# FOC_ESC_V1_1.net
KiCad netlist of a schematic drawn in Altium Designer
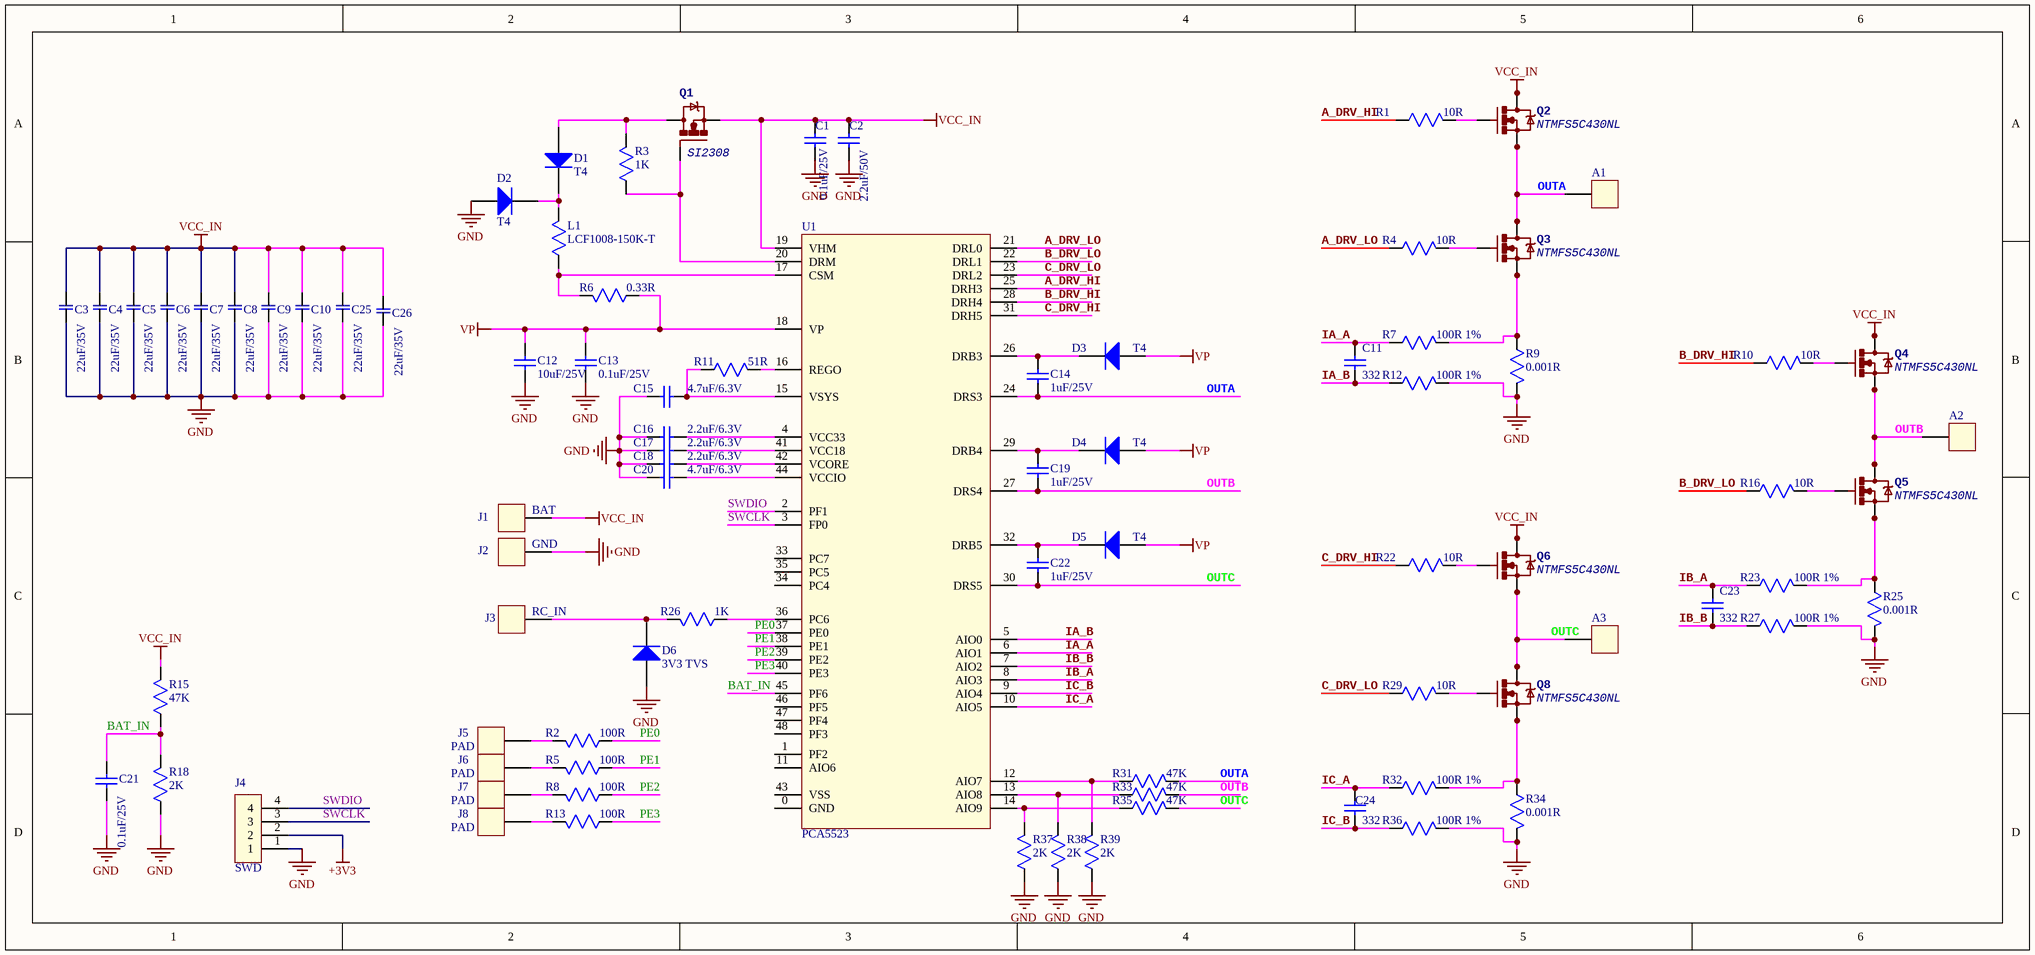
[diagram p0: FOC_ESC V1.1.SchDoc]

(export (version "E")
  (design (tool "Eeschema 10.0.6"))
  (components
    (comp (ref "A1") (value "~") (footprint "PAD-1  4*3") (libsource (lib "") (part "PAD_1")))
    (comp (ref "A2") (value "~") (footprint "PAD-1  4*3") (libsource (lib "") (part "PAD_1")))
    (comp (ref "A3") (value "~") (footprint "PAD-1  4*3") (libsource (lib "") (part "PAD_1")))
    (comp (ref "C1")
      (value "0.1uF/25V")
      (footprint "0603-RES")
      (fields (field (name "PUBLISHER") "Altium Limited"))
      (libsource (lib "DYS-XM30A V3.0") (part "Cap"))
    )
    (comp (ref "C2")
      (value "2.2uF/50V")
      (footprint "0805-RES")
      (fields (field (name "PUBLISHER") "Altium Limited"))
      (libsource (lib "DYS-XM30A V3.0") (part "Cap"))
    )
    (comp (ref "C3") (value "22uF/35V") (footprint "1206-RES") (libsource (lib "USER-2016") (part "C")))
    (comp (ref "C4") (value "22uF/35V") (footprint "1206-RES") (libsource (lib "USER-2016") (part "C")))
    (comp (ref "C5") (value "22uF/35V") (footprint "1206-RES") (libsource (lib "USER-2016") (part "C")))
    (comp (ref "C6") (value "22uF/35V") (footprint "1206-RES") (libsource (lib "USER-2016") (part "C")))
    (comp (ref "C7") (value "22uF/35V") (footprint "1206-RES") (libsource (lib "USER-2016") (part "C")))
    (comp (ref "C8") (value "22uF/35V") (footprint "1206-RES") (libsource (lib "USER-2016") (part "C")))
    (comp (ref "C9") (value "22uF/35V") (footprint "1206-RES") (libsource (lib "USER-2016") (part "C")))
    (comp (ref "C10") (value "22uF/35V") (footprint "1206-RES") (libsource (lib "USER-2016") (part "C")))
    (comp (ref "C11")
      (value "332")
      (footprint "0402-RES")
      (fields (field (name "PUBLISHER") "Altium Limited"))
      (libsource (lib "DYS-XM30A V3.0") (part "Cap"))
    )
    (comp (ref "C12")
      (value "10uF/25V")
      (footprint "0805-RES")
      (fields (field (name "PUBLISHER") "Altium Limited"))
      (libsource (lib "DYS-XM30A V3.0") (part "Cap"))
    )
    (comp (ref "C13")
      (value "0.1uF/25V")
      (footprint "0603-RES")
      (fields (field (name "PUBLISHER") "Altium Limited"))
      (libsource (lib "DYS-XM30A V3.0") (part "Cap"))
    )
    (comp (ref "C14")
      (value "1uF/25V")
      (footprint "0805-RES")
      (fields (field (name "PUBLISHER") "Altium Limited"))
      (libsource (lib "DYS-XM30A V3.0") (part "Cap"))
    )
    (comp (ref "C15")
      (value "4.7uF/6.3V")
      (footprint "0402-RES")
      (fields (field (name "PUBLISHER") "Altium Limited"))
      (libsource (lib "DYS-XM30A V3.0") (part "Cap"))
    )
    (comp (ref "C16")
      (value "2.2uF/6.3V")
      (footprint "0402-RES")
      (fields (field (name "PUBLISHER") "Altium Limited"))
      (libsource (lib "DYS-XM30A V3.0") (part "Cap"))
    )
    (comp (ref "C17")
      (value "2.2uF/6.3V")
      (footprint "0402-RES")
      (fields (field (name "PUBLISHER") "Altium Limited"))
      (libsource (lib "DYS-XM30A V3.0") (part "Cap"))
    )
    (comp (ref "C18")
      (value "2.2uF/6.3V")
      (footprint "0402-RES")
      (fields (field (name "PUBLISHER") "Altium Limited"))
      (libsource (lib "DYS-XM30A V3.0") (part "Cap"))
    )
    (comp (ref "C19")
      (value "1uF/25V")
      (footprint "0805-RES")
      (fields (field (name "PUBLISHER") "Altium Limited"))
      (libsource (lib "DYS-XM30A V3.0") (part "Cap"))
    )
    (comp (ref "C20")
      (value "4.7uF/6.3V")
      (footprint "0402-RES")
      (fields (field (name "PUBLISHER") "Altium Limited"))
      (libsource (lib "DYS-XM30A V3.0") (part "Cap"))
    )
    (comp (ref "C21")
      (value "0.1uF/25V")
      (footprint "0402-RES")
      (fields (field (name "PUBLISHER") "Altium Limited"))
      (libsource (lib "DYS-XM30A V3.0") (part "Cap"))
    )
    (comp (ref "C22")
      (value "1uF/25V")
      (footprint "0805-RES")
      (fields (field (name "PUBLISHER") "Altium Limited"))
      (libsource (lib "DYS-XM30A V3.0") (part "Cap"))
    )
    (comp (ref "C23")
      (value "332")
      (footprint "0402-RES")
      (fields (field (name "PUBLISHER") "Altium Limited"))
      (libsource (lib "DYS-XM30A V3.0") (part "Cap"))
    )
    (comp (ref "C24")
      (value "332")
      (footprint "0402-RES")
      (fields (field (name "PUBLISHER") "Altium Limited"))
      (libsource (lib "DYS-XM30A V3.0") (part "Cap"))
    )
    (comp (ref "C25") (value "22uF/35V") (footprint "1206-RES") (libsource (lib "USER-2016") (part "C")))
    (comp (ref "C26") (value "22uF/35V") (footprint "1206-RES") (libsource (lib "USER-2016") (part "C")))
    (comp (ref "D1")
      (value "T4")
      (footprint "SOD323")
      (fields (field (name "PUBLISHER") "Altium Limited"))
      (libsource (lib "DYS-XM30A V3.0") (part "Diode"))
    )
    (comp (ref "D2")
      (value "T4")
      (footprint "SOD323")
      (fields (field (name "PUBLISHER") "Altium Limited"))
      (libsource (lib "DYS-XM30A V3.0") (part "Diode"))
    )
    (comp (ref "D3")
      (value "T4")
      (footprint "SOD323")
      (fields (field (name "PUBLISHER") "Altium Limited"))
      (libsource (lib "DYS-XM30A V3.0") (part "Diode"))
    )
    (comp (ref "D4")
      (value "T4")
      (footprint "SOD323")
      (fields (field (name "PUBLISHER") "Altium Limited"))
      (libsource (lib "DYS-XM30A V3.0") (part "Diode"))
    )
    (comp (ref "D5")
      (value "T4")
      (footprint "SOD323")
      (fields (field (name "PUBLISHER") "Altium Limited"))
      (libsource (lib "DYS-XM30A V3.0") (part "Diode"))
    )
    (comp (ref "D6")
      (value "3V3 TVS")
      (footprint "SOD323")
      (fields (field (name "PUBLISHER") "Altium Limited"))
      (libsource (lib "DYS-XM30A V3.0") (part "Diode"))
    )
    (comp (ref "J1") (value "BAT") (footprint "PAD-1  4*3") (libsource (lib "USER-2016") (part "PAD")))
    (comp (ref "J2") (value "GND") (footprint "PAD-1  4*3") (libsource (lib "USER-2016") (part "PAD")))
    (comp (ref "J3") (value "RC_IN") (footprint "PAD-1  2*1.5") (libsource (lib "USER-2016") (part "PAD")))
    (comp (ref "J4") (value "SWD") (footprint "1.0-4p") (libsource (lib "USER-2016") (part "J_4P")))
    (comp (ref "J5") (value "PAD") (footprint "PAD-1  0.8*1.2") (libsource (lib "USER-2016") (part "PAD")))
    (comp (ref "J6") (value "PAD") (footprint "PAD-1  0.8*1.2") (libsource (lib "USER-2016") (part "PAD")))
    (comp (ref "J7") (value "PAD") (footprint "PAD-1  0.8*1.2") (libsource (lib "USER-2016") (part "PAD")))
    (comp (ref "J8") (value "PAD") (footprint "PAD-1  0.8*1.2") (libsource (lib "USER-2016") (part "PAD")))
    (comp (ref "L1")
      (value "LCF1008-150K-T")
      (footprint "LCF1008-RES")
      (libsource (lib "USER-2016") (part "R"))
    )
    (comp (ref "Q1") (value "SI2308") (footprint "SOT-23") (libsource (lib "USER-2016") (part "P-MOS")))
    (comp (ref "Q2")
      (value "NTMFS5C430NL")
      (footprint "DFN5*6")
      (libsource (lib "USER-2016") (part "AON7418"))
    )
    (comp (ref "Q3")
      (value "NTMFS5C430NL")
      (footprint "DFN5*6")
      (libsource (lib "USER-2016") (part "AON7418"))
    )
    (comp (ref "Q4")
      (value "NTMFS5C430NL")
      (footprint "DFN5*6")
      (libsource (lib "USER-2016") (part "AON7418"))
    )
    (comp (ref "Q5")
      (value "NTMFS5C430NL")
      (footprint "DFN5*6")
      (libsource (lib "USER-2016") (part "AON7418"))
    )
    (comp (ref "Q6")
      (value "NTMFS5C430NL")
      (footprint "DFN5*6")
      (libsource (lib "USER-2016") (part "AON7418"))
    )
    (comp (ref "Q8")
      (value "NTMFS5C430NL")
      (footprint "DFN5*6")
      (libsource (lib "USER-2016") (part "AON7418"))
    )
    (comp (ref "R1") (value "10R") (footprint "0402-RES") (libsource (lib "USER-2016") (part "R")))
    (comp (ref "R2") (value "100R") (footprint "0402-RES") (libsource (lib "USER-2016") (part "R")))
    (comp (ref "R3") (value "1K") (footprint "0402-RES") (libsource (lib "USER-2016") (part "R")))
    (comp (ref "R4") (value "10R") (footprint "0402-RES") (libsource (lib "USER-2016") (part "R")))
    (comp (ref "R5") (value "100R") (footprint "0402-RES") (libsource (lib "USER-2016") (part "R")))
    (comp (ref "R6") (value "0.33R") (footprint "0805-RES") (libsource (lib "USER-2016") (part "R")))
    (comp (ref "R7") (value "100R 1%") (footprint "0402-RES") (libsource (lib "USER-2016") (part "R")))
    (comp (ref "R8") (value "100R") (footprint "0402-RES") (libsource (lib "USER-2016") (part "R")))
    (comp (ref "R9") (value "0.001R") (footprint "2512-RES") (libsource (lib "USER-2016") (part "R")))
    (comp (ref "R10") (value "10R") (footprint "0402-RES") (libsource (lib "USER-2016") (part "R")))
    (comp (ref "R11") (value "51R") (footprint "0402-RES") (libsource (lib "USER-2016") (part "R")))
    (comp (ref "R12") (value "100R 1%") (footprint "0402-RES") (libsource (lib "USER-2016") (part "R")))
    (comp (ref "R13") (value "100R") (footprint "0402-RES") (libsource (lib "USER-2016") (part "R")))
    (comp (ref "R15") (value "47K") (footprint "0402-RES") (libsource (lib "USER-2016") (part "R")))
    (comp (ref "R16") (value "10R") (footprint "0402-RES") (libsource (lib "USER-2016") (part "R")))
    (comp (ref "R18") (value "2K") (footprint "0402-RES") (libsource (lib "USER-2016") (part "R")))
    (comp (ref "R22") (value "10R") (footprint "0402-RES") (libsource (lib "USER-2016") (part "R")))
    (comp (ref "R23") (value "100R 1%") (footprint "0402-RES") (libsource (lib "USER-2016") (part "R")))
    (comp (ref "R25") (value "0.001R") (footprint "2512-RES") (libsource (lib "USER-2016") (part "R")))
    (comp (ref "R26") (value "1K") (footprint "0402-RES") (libsource (lib "USER-2016") (part "R")))
    (comp (ref "R27") (value "100R 1%") (footprint "0402-RES") (libsource (lib "USER-2016") (part "R")))
    (comp (ref "R29") (value "10R") (footprint "0402-RES") (libsource (lib "USER-2016") (part "R")))
    (comp (ref "R31") (value "47K") (footprint "0402-RES") (libsource (lib "USER-2016") (part "R")))
    (comp (ref "R32") (value "100R 1%") (footprint "0402-RES") (libsource (lib "USER-2016") (part "R")))
    (comp (ref "R33") (value "47K") (footprint "0402-RES") (libsource (lib "USER-2016") (part "R")))
    (comp (ref "R34") (value "0.001R") (footprint "2512-RES") (libsource (lib "USER-2016") (part "R")))
    (comp (ref "R35") (value "47K") (footprint "0402-RES") (libsource (lib "USER-2016") (part "R")))
    (comp (ref "R36") (value "100R 1%") (footprint "0402-RES") (libsource (lib "USER-2016") (part "R")))
    (comp (ref "R37") (value "2K") (footprint "0402-RES") (libsource (lib "USER-2016") (part "R")))
    (comp (ref "R38") (value "2K") (footprint "0402-RES") (libsource (lib "USER-2016") (part "R")))
    (comp (ref "R39") (value "2K") (footprint "0402-RES") (libsource (lib "USER-2016") (part "R")))
    (comp (ref "U1") (value "PCA5523") (footprint "QFN48") (libsource (lib "USER-2016") (part "PCA5523")))
  )
  (nets
    (net (code "1") (name "+3V3") (class "Default")
      (node (ref "J4") (pin "2") (pinfunction "2_2") (pintype "passive"))
    )
    (net (code "2") (name "/A_DRV_HI") (class "Default")
      (node (ref "R1") (pin "1") (pinfunction "1_1") (pintype "passive"))
      (node (ref "U1") (pin "25") (pinfunction "DRH3_25") (pintype "passive"))
    )
    (net (code "3") (name "/A_DRV_LO") (class "Default")
      (node (ref "R4") (pin "1") (pinfunction "1_1") (pintype "passive"))
      (node (ref "U1") (pin "21") (pinfunction "DRL0_21") (pintype "passive"))
    )
    (net (code "4") (name "/BAT_IN") (class "Default")
      (node (ref "C21") (pin "1") (pinfunction "1_1") (pintype "passive"))
      (node (ref "R15") (pin "1") (pinfunction "1_1") (pintype "passive"))
      (node (ref "R18") (pin "2") (pinfunction "2_2") (pintype "passive"))
      (node (ref "U1") (pin "45") (pinfunction "PF6_45") (pintype "passive"))
    )
    (net (code "5") (name "/B_DRV_HI") (class "Default")
      (node (ref "R10") (pin "1") (pinfunction "1_1") (pintype "passive"))
      (node (ref "U1") (pin "28") (pinfunction "DRH4_28") (pintype "passive"))
    )
    (net (code "6") (name "/B_DRV_LO") (class "Default")
      (node (ref "R16") (pin "1") (pinfunction "1_1") (pintype "passive"))
      (node (ref "U1") (pin "22") (pinfunction "DRL1_22") (pintype "passive"))
    )
    (net (code "7") (name "/C_DRV_HI") (class "Default")
      (node (ref "R22") (pin "1") (pinfunction "1_1") (pintype "passive"))
      (node (ref "U1") (pin "31") (pinfunction "DRH5_31") (pintype "passive"))
    )
    (net (code "8") (name "/C_DRV_LO") (class "Default")
      (node (ref "R29") (pin "1") (pinfunction "1_1") (pintype "passive"))
      (node (ref "U1") (pin "23") (pinfunction "DRL2_23") (pintype "passive"))
    )
    (net (code "9") (name "/IA_A") (class "Default")
      (node (ref "C11") (pin "1") (pinfunction "1_1") (pintype "passive"))
      (node (ref "R7") (pin "1") (pinfunction "1_1") (pintype "passive"))
      (node (ref "U1") (pin "6") (pinfunction "AIO1_6") (pintype "passive"))
    )
    (net (code "10") (name "/IA_B") (class "Default")
      (node (ref "C11") (pin "2") (pinfunction "2_2") (pintype "passive"))
      (node (ref "R12") (pin "1") (pinfunction "1_1") (pintype "passive"))
      (node (ref "U1") (pin "5") (pinfunction "AIO0_5") (pintype "passive"))
    )
    (net (code "11") (name "/IB_A") (class "Default")
      (node (ref "C23") (pin "1") (pinfunction "1_1") (pintype "passive"))
      (node (ref "R23") (pin "1") (pinfunction "1_1") (pintype "passive"))
      (node (ref "U1") (pin "8") (pinfunction "AIO3_8") (pintype "passive"))
    )
    (net (code "12") (name "/IB_B") (class "Default")
      (node (ref "C23") (pin "2") (pinfunction "2_2") (pintype "passive"))
      (node (ref "R27") (pin "1") (pinfunction "1_1") (pintype "passive"))
      (node (ref "U1") (pin "7") (pinfunction "AIO2_7") (pintype "passive"))
    )
    (net (code "13") (name "/IC_A") (class "Default")
      (node (ref "C24") (pin "1") (pinfunction "1_1") (pintype "passive"))
      (node (ref "R32") (pin "1") (pinfunction "1_1") (pintype "passive"))
      (node (ref "U1") (pin "10") (pinfunction "AIO5_10") (pintype "passive"))
    )
    (net (code "14") (name "/IC_B") (class "Default")
      (node (ref "C24") (pin "2") (pinfunction "2_2") (pintype "passive"))
      (node (ref "R36") (pin "1") (pinfunction "1_1") (pintype "passive"))
      (node (ref "U1") (pin "9") (pinfunction "AIO4_9") (pintype "passive"))
    )
    (net (code "15") (name "/OUTA") (class "Default")
      (node (ref "A1") (pin "1") (pinfunction "1_1") (pintype "passive"))
      (node (ref "C14") (pin "2") (pinfunction "2_2") (pintype "passive"))
      (node (ref "Q2") (pin "3") (pinfunction "S_3") (pintype "passive"))
      (node (ref "Q3") (pin "5") (pinfunction "D_5") (pintype "passive"))
      (node (ref "R31") (pin "2") (pinfunction "2_2") (pintype "passive"))
      (node (ref "U1") (pin "24") (pinfunction "DRS3_24") (pintype "passive"))
    )
    (net (code "16") (name "/OUTB") (class "Default")
      (node (ref "A2") (pin "1") (pinfunction "1_1") (pintype "passive"))
      (node (ref "C19") (pin "2") (pinfunction "2_2") (pintype "passive"))
      (node (ref "Q4") (pin "3") (pinfunction "S_3") (pintype "passive"))
      (node (ref "Q5") (pin "5") (pinfunction "D_5") (pintype "passive"))
      (node (ref "R33") (pin "2") (pinfunction "2_2") (pintype "passive"))
      (node (ref "U1") (pin "27") (pinfunction "DRS4_27") (pintype "passive"))
    )
    (net (code "17") (name "/OUTC") (class "Default")
      (node (ref "A3") (pin "1") (pinfunction "1_1") (pintype "passive"))
      (node (ref "C22") (pin "2") (pinfunction "2_2") (pintype "passive"))
      (node (ref "Q6") (pin "3") (pinfunction "S_3") (pintype "passive"))
      (node (ref "Q8") (pin "5") (pinfunction "D_5") (pintype "passive"))
      (node (ref "R35") (pin "2") (pinfunction "2_2") (pintype "passive"))
      (node (ref "U1") (pin "30") (pinfunction "DRS5_30") (pintype "passive"))
    )
    (net (code "18") (name "/PE0") (class "Default")
      (node (ref "R2") (pin "1") (pinfunction "1_1") (pintype "passive"))
      (node (ref "U1") (pin "37") (pinfunction "PE0_37") (pintype "passive"))
    )
    (net (code "19") (name "/PE1") (class "Default")
      (node (ref "R5") (pin "1") (pinfunction "1_1") (pintype "passive"))
      (node (ref "U1") (pin "38") (pinfunction "PE1_38") (pintype "passive"))
    )
    (net (code "20") (name "/PE2") (class "Default")
      (node (ref "R8") (pin "1") (pinfunction "1_1") (pintype "passive"))
      (node (ref "U1") (pin "39") (pinfunction "PE2_39") (pintype "passive"))
    )
    (net (code "21") (name "/PE3") (class "Default")
      (node (ref "R13") (pin "1") (pinfunction "1_1") (pintype "passive"))
      (node (ref "U1") (pin "40") (pinfunction "PE3_40") (pintype "passive"))
    )
    (net (code "22") (name "/SWCLK") (class "Default")
      (node (ref "J4") (pin "3") (pinfunction "3_3") (pintype "passive"))
      (node (ref "U1") (pin "3") (pinfunction "FP0_3") (pintype "passive"))
    )
    (net (code "23") (name "/SWDIO") (class "Default")
      (node (ref "J4") (pin "4") (pinfunction "4_4") (pintype "passive"))
      (node (ref "U1") (pin "2") (pinfunction "PF1_2") (pintype "passive"))
    )
    (net (code "24") (name "GND") (class "Default")
      (node (ref "C1") (pin "2") (pinfunction "2_2") (pintype "passive"))
      (node (ref "C10") (pin "2") (pinfunction "2_2") (pintype "passive"))
      (node (ref "C12") (pin "2") (pinfunction "2_2") (pintype "passive"))
      (node (ref "C13") (pin "2") (pinfunction "2_2") (pintype "passive"))
      (node (ref "C15") (pin "1") (pinfunction "1_1") (pintype "passive"))
      (node (ref "C16") (pin "1") (pinfunction "1_1") (pintype "passive"))
      (node (ref "C17") (pin "1") (pinfunction "1_1") (pintype "passive"))
      (node (ref "C18") (pin "1") (pinfunction "1_1") (pintype "passive"))
      (node (ref "C2") (pin "2") (pinfunction "2_2") (pintype "passive"))
      (node (ref "C20") (pin "1") (pinfunction "1_1") (pintype "passive"))
      (node (ref "C21") (pin "2") (pinfunction "2_2") (pintype "passive"))
      (node (ref "C25") (pin "2") (pinfunction "2_2") (pintype "passive"))
      (node (ref "C26") (pin "2") (pinfunction "2_2") (pintype "passive"))
      (node (ref "C3") (pin "2") (pinfunction "2_2") (pintype "passive"))
      (node (ref "C4") (pin "2") (pinfunction "2_2") (pintype "passive"))
      (node (ref "C5") (pin "2") (pinfunction "2_2") (pintype "passive"))
      (node (ref "C6") (pin "2") (pinfunction "2_2") (pintype "passive"))
      (node (ref "C7") (pin "2") (pinfunction "2_2") (pintype "passive"))
      (node (ref "C8") (pin "2") (pinfunction "2_2") (pintype "passive"))
      (node (ref "C9") (pin "2") (pinfunction "2_2") (pintype "passive"))
      (node (ref "D2") (pin "1") (pinfunction "A_1") (pintype "passive"))
      (node (ref "D6") (pin "1") (pinfunction "A_1") (pintype "passive"))
      (node (ref "J2") (pin "1") (pinfunction "1_1") (pintype "passive"))
      (node (ref "J4") (pin "1") (pinfunction "1_1") (pintype "passive"))
      (node (ref "R12") (pin "2") (pinfunction "2_2") (pintype "passive"))
      (node (ref "R18") (pin "1") (pinfunction "1_1") (pintype "passive"))
      (node (ref "R25") (pin "2") (pinfunction "2_2") (pintype "passive"))
      (node (ref "R27") (pin "2") (pinfunction "2_2") (pintype "passive"))
      (node (ref "R34") (pin "2") (pinfunction "2_2") (pintype "passive"))
      (node (ref "R36") (pin "2") (pinfunction "2_2") (pintype "passive"))
      (node (ref "R37") (pin "1") (pinfunction "1_1") (pintype "passive"))
      (node (ref "R38") (pin "1") (pinfunction "1_1") (pintype "passive"))
      (node (ref "R39") (pin "1") (pinfunction "1_1") (pintype "passive"))
      (node (ref "R9") (pin "2") (pinfunction "2_2") (pintype "passive"))
    )
    (net (code "25") (name "Net-(D1-A)") (class "Default")
      (node (ref "D1") (pin "1") (pinfunction "A_1") (pintype "passive"))
      (node (ref "Q1") (pin "3") (pinfunction "D_3") (pintype "passive"))
      (node (ref "R3") (pin "2") (pinfunction "2_2") (pintype "passive"))
    )
    (net (code "26") (name "Net-(D1-K)") (class "Default")
      (node (ref "D1") (pin "2") (pinfunction "K_2") (pintype "passive"))
      (node (ref "D2") (pin "2") (pinfunction "K_2") (pintype "passive"))
      (node (ref "L1") (pin "2") (pinfunction "2_2") (pintype "passive"))
    )
    (net (code "27") (name "Net-(D3-K)") (class "Default")
      (node (ref "C14") (pin "1") (pinfunction "1_1") (pintype "passive"))
      (node (ref "D3") (pin "2") (pinfunction "K_2") (pintype "passive"))
      (node (ref "U1") (pin "26") (pinfunction "DRB3_26") (pintype "passive"))
    )
    (net (code "28") (name "Net-(D4-K)") (class "Default")
      (node (ref "C19") (pin "1") (pinfunction "1_1") (pintype "passive"))
      (node (ref "D4") (pin "2") (pinfunction "K_2") (pintype "passive"))
      (node (ref "U1") (pin "29") (pinfunction "DRB4_29") (pintype "passive"))
    )
    (net (code "29") (name "Net-(D5-K)") (class "Default")
      (node (ref "C22") (pin "1") (pinfunction "1_1") (pintype "passive"))
      (node (ref "D5") (pin "2") (pinfunction "K_2") (pintype "passive"))
      (node (ref "U1") (pin "32") (pinfunction "DRB5_32") (pintype "passive"))
    )
    (net (code "30") (name "Net-(D6-K)") (class "Default")
      (node (ref "D6") (pin "2") (pinfunction "K_2") (pintype "passive"))
      (node (ref "J3") (pin "1") (pinfunction "1_1") (pintype "passive"))
      (node (ref "R26") (pin "2") (pinfunction "2_2") (pintype "passive"))
    )
    (net (code "31") (name "Net-(J5-Pad1)") (class "Default")
      (node (ref "J5") (pin "1") (pinfunction "1_1") (pintype "passive"))
      (node (ref "R2") (pin "2") (pinfunction "2_2") (pintype "passive"))
    )
    (net (code "32") (name "Net-(J6-Pad1)") (class "Default")
      (node (ref "J6") (pin "1") (pinfunction "1_1") (pintype "passive"))
      (node (ref "R5") (pin "2") (pinfunction "2_2") (pintype "passive"))
    )
    (net (code "33") (name "Net-(J7-Pad1)") (class "Default")
      (node (ref "J7") (pin "1") (pinfunction "1_1") (pintype "passive"))
      (node (ref "R8") (pin "2") (pinfunction "2_2") (pintype "passive"))
    )
    (net (code "34") (name "Net-(J8-Pad1)") (class "Default")
      (node (ref "J8") (pin "1") (pinfunction "1_1") (pintype "passive"))
      (node (ref "R13") (pin "2") (pinfunction "2_2") (pintype "passive"))
    )
    (net (code "35") (name "Net-(Q1-G)") (class "Default")
      (node (ref "Q1") (pin "1") (pinfunction "G_1") (pintype "passive"))
      (node (ref "R3") (pin "1") (pinfunction "1_1") (pintype "passive"))
      (node (ref "U1") (pin "20") (pinfunction "DRM_20") (pintype "passive"))
    )
    (net (code "36") (name "Net-(Q2-G)") (class "Default")
      (node (ref "Q2") (pin "4") (pinfunction "G_4") (pintype "passive"))
      (node (ref "R1") (pin "2") (pinfunction "2_2") (pintype "passive"))
    )
    (net (code "37") (name "Net-(Q3-G)") (class "Default")
      (node (ref "Q3") (pin "4") (pinfunction "G_4") (pintype "passive"))
      (node (ref "R4") (pin "2") (pinfunction "2_2") (pintype "passive"))
    )
    (net (code "38") (name "Net-(Q3-S)") (class "Default")
      (node (ref "Q3") (pin "3") (pinfunction "S_3") (pintype "passive"))
      (node (ref "R7") (pin "2") (pinfunction "2_2") (pintype "passive"))
      (node (ref "R9") (pin "1") (pinfunction "1_1") (pintype "passive"))
    )
    (net (code "39") (name "Net-(Q4-G)") (class "Default")
      (node (ref "Q4") (pin "4") (pinfunction "G_4") (pintype "passive"))
      (node (ref "R10") (pin "2") (pinfunction "2_2") (pintype "passive"))
    )
    (net (code "40") (name "Net-(Q5-G)") (class "Default")
      (node (ref "Q5") (pin "4") (pinfunction "G_4") (pintype "passive"))
      (node (ref "R16") (pin "2") (pinfunction "2_2") (pintype "passive"))
    )
    (net (code "41") (name "Net-(Q5-S)") (class "Default")
      (node (ref "Q5") (pin "3") (pinfunction "S_3") (pintype "passive"))
      (node (ref "R23") (pin "2") (pinfunction "2_2") (pintype "passive"))
      (node (ref "R25") (pin "1") (pinfunction "1_1") (pintype "passive"))
    )
    (net (code "42") (name "Net-(Q6-G)") (class "Default")
      (node (ref "Q6") (pin "4") (pinfunction "G_4") (pintype "passive"))
      (node (ref "R22") (pin "2") (pinfunction "2_2") (pintype "passive"))
    )
    (net (code "43") (name "Net-(Q8-G)") (class "Default")
      (node (ref "Q8") (pin "4") (pinfunction "G_4") (pintype "passive"))
      (node (ref "R29") (pin "2") (pinfunction "2_2") (pintype "passive"))
    )
    (net (code "44") (name "Net-(Q8-S)") (class "Default")
      (node (ref "Q8") (pin "3") (pinfunction "S_3") (pintype "passive"))
      (node (ref "R32") (pin "2") (pinfunction "2_2") (pintype "passive"))
      (node (ref "R34") (pin "1") (pinfunction "1_1") (pintype "passive"))
    )
    (net (code "45") (name "Net-(U1-AIO7)") (class "Default")
      (node (ref "R31") (pin "1") (pinfunction "1_1") (pintype "passive"))
      (node (ref "R39") (pin "2") (pinfunction "2_2") (pintype "passive"))
      (node (ref "U1") (pin "12") (pinfunction "AIO7_12") (pintype "passive"))
    )
    (net (code "46") (name "Net-(U1-AIO8)") (class "Default")
      (node (ref "R33") (pin "1") (pinfunction "1_1") (pintype "passive"))
      (node (ref "R38") (pin "2") (pinfunction "2_2") (pintype "passive"))
      (node (ref "U1") (pin "13") (pinfunction "AIO8_13") (pintype "passive"))
    )
    (net (code "47") (name "Net-(U1-AIO9)") (class "Default")
      (node (ref "R35") (pin "1") (pinfunction "1_1") (pintype "passive"))
      (node (ref "R37") (pin "2") (pinfunction "2_2") (pintype "passive"))
      (node (ref "U1") (pin "14") (pinfunction "AIO9_14") (pintype "passive"))
    )
    (net (code "48") (name "Net-(U1-CSM)") (class "Default")
      (node (ref "L1") (pin "1") (pinfunction "1_1") (pintype "passive"))
      (node (ref "R6") (pin "2") (pinfunction "2_2") (pintype "passive"))
      (node (ref "U1") (pin "17") (pinfunction "CSM_17") (pintype "passive"))
    )
    (net (code "49") (name "Net-(U1-PC6)") (class "Default")
      (node (ref "R26") (pin "1") (pinfunction "1_1") (pintype "passive"))
      (node (ref "U1") (pin "36") (pinfunction "PC6_36") (pintype "passive"))
    )
    (net (code "50") (name "Net-(U1-REGO)") (class "Default")
      (node (ref "R11") (pin "2") (pinfunction "2_2") (pintype "passive"))
      (node (ref "U1") (pin "16") (pinfunction "REGO_16") (pintype "passive"))
    )
    (net (code "51") (name "Net-(U1-VCC18)") (class "Default")
      (node (ref "C17") (pin "2") (pinfunction "2_2") (pintype "passive"))
      (node (ref "U1") (pin "41") (pinfunction "VCC18_41") (pintype "passive"))
    )
    (net (code "52") (name "Net-(U1-VCC33)") (class "Default")
      (node (ref "C16") (pin "2") (pinfunction "2_2") (pintype "passive"))
      (node (ref "U1") (pin "4") (pinfunction "VCC33_4") (pintype "passive"))
    )
    (net (code "53") (name "Net-(U1-VCCIO)") (class "Default")
      (node (ref "C20") (pin "2") (pinfunction "2_2") (pintype "passive"))
      (node (ref "U1") (pin "44") (pinfunction "VCCIO_44") (pintype "passive"))
    )
    (net (code "54") (name "Net-(U1-VCORE)") (class "Default")
      (node (ref "C18") (pin "2") (pinfunction "2_2") (pintype "passive"))
      (node (ref "U1") (pin "42") (pinfunction "VCORE_42") (pintype "passive"))
    )
    (net (code "55") (name "Net-(U1-VSYS)") (class "Default")
      (node (ref "C15") (pin "2") (pinfunction "2_2") (pintype "passive"))
      (node (ref "R11") (pin "1") (pinfunction "1_1") (pintype "passive"))
      (node (ref "U1") (pin "15") (pinfunction "VSYS_15") (pintype "passive"))
    )
    (net (code "56") (name "VCC_IN") (class "Default")
      (node (ref "C1") (pin "1") (pinfunction "1_1") (pintype "passive"))
      (node (ref "C10") (pin "1") (pinfunction "1_1") (pintype "passive"))
      (node (ref "C2") (pin "1") (pinfunction "1_1") (pintype "passive"))
      (node (ref "C25") (pin "1") (pinfunction "1_1") (pintype "passive"))
      (node (ref "C26") (pin "1") (pinfunction "1_1") (pintype "passive"))
      (node (ref "C3") (pin "1") (pinfunction "1_1") (pintype "passive"))
      (node (ref "C4") (pin "1") (pinfunction "1_1") (pintype "passive"))
      (node (ref "C5") (pin "1") (pinfunction "1_1") (pintype "passive"))
      (node (ref "C6") (pin "1") (pinfunction "1_1") (pintype "passive"))
      (node (ref "C7") (pin "1") (pinfunction "1_1") (pintype "passive"))
      (node (ref "C8") (pin "1") (pinfunction "1_1") (pintype "passive"))
      (node (ref "C9") (pin "1") (pinfunction "1_1") (pintype "passive"))
      (node (ref "J1") (pin "1") (pinfunction "1_1") (pintype "passive"))
      (node (ref "Q1") (pin "2") (pinfunction "S_2") (pintype "passive"))
      (node (ref "Q2") (pin "5") (pinfunction "D_5") (pintype "passive"))
      (node (ref "Q4") (pin "5") (pinfunction "D_5") (pintype "passive"))
      (node (ref "Q6") (pin "5") (pinfunction "D_5") (pintype "passive"))
      (node (ref "R15") (pin "2") (pinfunction "2_2") (pintype "passive"))
      (node (ref "U1") (pin "19") (pinfunction "VHM_19") (pintype "passive"))
    )
    (net (code "57") (name "VP") (class "Default")
      (node (ref "C12") (pin "1") (pinfunction "1_1") (pintype "passive"))
      (node (ref "C13") (pin "1") (pinfunction "1_1") (pintype "passive"))
      (node (ref "D3") (pin "1") (pinfunction "A_1") (pintype "passive"))
      (node (ref "D4") (pin "1") (pinfunction "A_1") (pintype "passive"))
      (node (ref "D5") (pin "1") (pinfunction "A_1") (pintype "passive"))
      (node (ref "R6") (pin "1") (pinfunction "1_1") (pintype "passive"))
      (node (ref "U1") (pin "18") (pinfunction "VP_18") (pintype "passive"))
    )
    (net (code "58") (name "unconnected-(J4-GND-Pad0)") (class "Default")
      (node (ref "J4") (pin "0") (pinfunction "GND_0") (pintype "power_in"))
    )
    (net (code "59") (name "unconnected-(U1-AIO6-Pad11)") (class "Default")
      (node (ref "U1") (pin "11") (pinfunction "AIO6_11") (pintype "passive"))
    )
    (net (code "60") (name "unconnected-(U1-GND-Pad0)") (class "Default")
      (node (ref "U1") (pin "0") (pinfunction "GND_0") (pintype "passive"))
    )
    (net (code "61") (name "unconnected-(U1-PC4-Pad34)") (class "Default")
      (node (ref "U1") (pin "34") (pinfunction "PC4_34") (pintype "passive"))
    )
    (net (code "62") (name "unconnected-(U1-PC5-Pad35)") (class "Default")
      (node (ref "U1") (pin "35") (pinfunction "PC5_35") (pintype "passive"))
    )
    (net (code "63") (name "unconnected-(U1-PC7-Pad33)") (class "Default")
      (node (ref "U1") (pin "33") (pinfunction "PC7_33") (pintype "passive"))
    )
    (net (code "64") (name "unconnected-(U1-PF2-Pad1)") (class "Default")
      (node (ref "U1") (pin "1") (pinfunction "PF2_1") (pintype "passive"))
    )
    (net (code "65") (name "unconnected-(U1-PF3-Pad48)") (class "Default")
      (node (ref "U1") (pin "48") (pinfunction "PF3_48") (pintype "passive"))
    )
    (net (code "66") (name "unconnected-(U1-PF4-Pad47)") (class "Default")
      (node (ref "U1") (pin "47") (pinfunction "PF4_47") (pintype "passive"))
    )
    (net (code "67") (name "unconnected-(U1-PF5-Pad46)") (class "Default")
      (node (ref "U1") (pin "46") (pinfunction "PF5_46") (pintype "passive"))
    )
    (net (code "68") (name "unconnected-(U1-VSS-Pad43)") (class "Default")
      (node (ref "U1") (pin "43") (pinfunction "VSS_43") (pintype "passive"))
    )
  )
)
